# Sheet1.net
KiCad netlist of a schematic drawn in Altium Designer
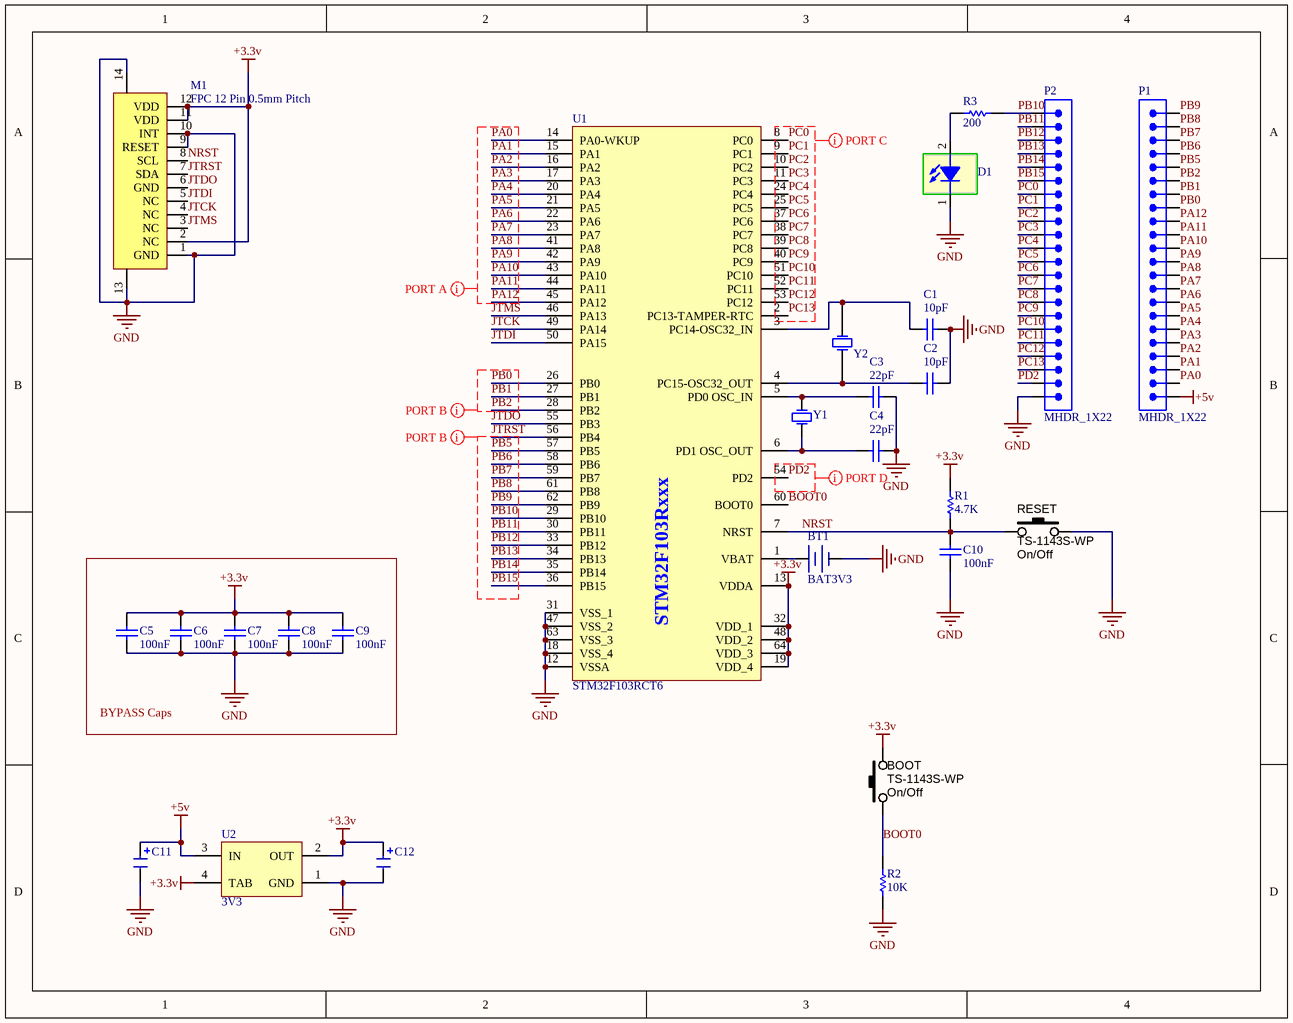
[diagram p0: Sheet1.SchDoc]

(export (version "E")
  (design (tool "Eeschema 10.0.6"))
  (components
    (comp (ref "BOOT")
      (value "TS-1143S-WP")
      (footprint "TS-1143S")
      (description "Switch SMD Tact 4.3mm Stem")
      (fields (field (name "FUNCTION") "On/Off"))
      (libsource (lib "Schematic") (part "SW_SMD_PB_4.3mm"))
    )
    (comp (ref "BT1")
      (value "BAT3V3")
      (footprint "Battery socket SMD")
      (description "Battry Backup")
      (fields (field (name "DESIGNER") "Abbas Basereh"))
      (libsource (lib "ALMA") (part "Battry Backup"))
    )
    (comp (ref "C1")
      (value "10pF")
      (footprint "0805 C")
      (description "CAP 0805")
      (fields (field (name "DESIGNER") "Abbas Basereh"))
      (libsource (lib "ALMA") (part "CAP SMD 0805"))
    )
    (comp (ref "C2")
      (value "10pF")
      (footprint "0805 C")
      (description "CAP 0805")
      (fields (field (name "DESIGNER") "Abbas Basereh"))
      (libsource (lib "ALMA") (part "CAP SMD 0805"))
    )
    (comp (ref "C3")
      (value "22pF")
      (footprint "0805 C")
      (description "CAP 0805")
      (fields (field (name "DESIGNER") "Abbas Basereh"))
      (libsource (lib "ALMA") (part "CAP SMD 0805"))
    )
    (comp (ref "C4")
      (value "22pF")
      (footprint "0805 C")
      (description "CAP 0805")
      (fields (field (name "DESIGNER") "Abbas Basereh"))
      (libsource (lib "ALMA") (part "CAP SMD 0805"))
    )
    (comp (ref "C5")
      (value "100nF")
      (footprint "0805 C")
      (description "CAP 0805")
      (fields (field (name "DESIGNER") "Abbas Basereh"))
      (libsource (lib "ALMA") (part "CAP SMD 0805"))
    )
    (comp (ref "C6")
      (value "100nF")
      (footprint "0805 C")
      (description "CAP 0805")
      (fields (field (name "DESIGNER") "Abbas Basereh"))
      (libsource (lib "ALMA") (part "CAP SMD 0805"))
    )
    (comp (ref "C7")
      (value "100nF")
      (footprint "0805 C")
      (description "CAP 0805")
      (fields (field (name "DESIGNER") "Abbas Basereh"))
      (libsource (lib "ALMA") (part "CAP SMD 0805"))
    )
    (comp (ref "C8")
      (value "100nF")
      (footprint "0805 C")
      (description "CAP 0805")
      (fields (field (name "DESIGNER") "Abbas Basereh"))
      (libsource (lib "ALMA") (part "CAP SMD 0805"))
    )
    (comp (ref "C9")
      (value "100nF")
      (footprint "0805 C")
      (description "CAP 0805")
      (fields (field (name "DESIGNER") "Abbas Basereh"))
      (libsource (lib "ALMA") (part "CAP SMD 0805"))
    )
    (comp (ref "C10")
      (value "100nF")
      (footprint "0805 C")
      (description "CAP 0805")
      (fields (field (name "DESIGNER") "Abbas Basereh"))
      (libsource (lib "ALMA") (part "CAP SMD 0805"))
    )
    (comp (ref "C11")
      (value "Tantalium Cap")
      (footprint "TANTAL-CAP-Size D")
      (libsource (lib "ALMA") (part "Capacitor Tantalium"))
    )
    (comp (ref "C12")
      (value "Tantalium Cap")
      (footprint "TANTAL-CAP-Size D")
      (libsource (lib "ALMA") (part "Capacitor Tantalium"))
    )
    (comp (ref "D1")
      (value "SMD 1206 LED")
      (footprint "LED 1206")
      (libsource (lib "Schematic") (part "LED SMD 1206"))
    )
    (comp (ref "M1")
      (value "FPC 12 Pin 0.5mm Pitch")
      (footprint "FPC 12 Pin 0.5mm Pitch")
      (libsource (lib "ZetaBoard_Lib") (part "FPC 12 Pin 0.5mm Pitch"))
    )
    (comp (ref "P1")
      (value "MHDR_1X22")
      (footprint "HDR1X22")
      (description "Male Header 1X22")
      (libsource (lib "Schematic") (part "MHDR_1X22"))
    )
    (comp (ref "P2")
      (value "MHDR_1X22")
      (footprint "HDR1X22")
      (description "Male Header 1X22")
      (libsource (lib "Schematic") (part "MHDR_1X22"))
    )
    (comp (ref "R1")
      (value "4.7K")
      (footprint "0805 R")
      (description "RES 0805")
      (fields (field (name "DESIGNER") "Abbas Basereh"))
      (libsource (lib "ALMA") (part "RES 0805 0.125W"))
    )
    (comp (ref "R2")
      (value "10K")
      (footprint "0805 R")
      (description "RES 0805")
      (fields (field (name "DESIGNER") "Abbas Basereh"))
      (libsource (lib "ALMA") (part "RES 0805 0.125W"))
    )
    (comp (ref "R3")
      (value "200")
      (footprint "0805 R")
      (description "RES 0805")
      (fields (field (name "DESIGNER") "Abbas Basereh"))
      (libsource (lib "ALMA") (part "RES 0805 0.125W"))
    )
    (comp (ref "RESET")
      (value "TS-1143S-WP")
      (footprint "TS-1143S")
      (description "Switch SMD Tact 4.3mm Stem")
      (fields (field (name "FUNCTION") "On/Off"))
      (libsource (lib "Schematic") (part "SW_SMD_PB_4.3mm"))
    )
    (comp (ref "U1")
      (value "STM32F103RCT6")
      (footprint "LQFP-64")
      (libsource (lib "ALMA") (part "STM32F103Rxxx"))
    )
    (comp (ref "U2")
      (value "3V3")
      (footprint "SOT223")
      (description "x.x Volt, 800mA Low-Dropout Linear Regulator, 4-pin SOT-223")
      (fields (field (name "DESIGNER") "Ali Hafizi"))
      (libsource (lib "Schematic") (part "AMS1117-x.x"))
    )
    (comp (ref "Y1")
      (value "16 MHz")
      (footprint "Xtal SMD")
      (description "XTAL Crystal")
      (fields (field (name "DESIGNER") "ABBAS BASEREH"))
      (libsource (lib "ALMA") (part "XTAL"))
    )
    (comp (ref "Y2")
      (value "11.0592 MHz")
      (footprint "Xtal 32.782khz")
      (description "XTAL Crystal")
      (fields (field (name "DESIGNER") "Eng. Saeid Jorablo") (field (name "PUBLISHER") "SJ Unlimited"))
      (libsource (lib "Schematic") (part "XTAL_Crystal"))
    )
  )
  (nets
    (net (code "1") (name "+3.3v") (class "Default")
      (node (ref "BOOT") (pin "2") (pintype "passive"))
      (node (ref "C12") (pin "1") (pintype "passive"))
      (node (ref "C5") (pin "1") (pinfunction "1_1") (pintype "passive"))
      (node (ref "C6") (pin "1") (pinfunction "1_1") (pintype "passive"))
      (node (ref "C7") (pin "1") (pinfunction "1_1") (pintype "passive"))
      (node (ref "C8") (pin "1") (pinfunction "1_1") (pintype "passive"))
      (node (ref "C9") (pin "1") (pinfunction "1_1") (pintype "passive"))
      (node (ref "M1") (pin "11") (pinfunction "VDD_11") (pintype "passive"))
      (node (ref "M1") (pin "12") (pinfunction "VDD_12") (pintype "passive"))
      (node (ref "M1") (pin "2") (pinfunction "NC_2") (pintype "passive"))
      (node (ref "R1") (pin "2") (pinfunction "2_2") (pintype "passive"))
      (node (ref "U1") (pin "13") (pinfunction "VDDA_13") (pintype "passive"))
      (node (ref "U1") (pin "19") (pinfunction "VDD_4_19") (pintype "passive"))
      (node (ref "U1") (pin "32") (pinfunction "VDD_1_32") (pintype "passive"))
      (node (ref "U1") (pin "48") (pinfunction "VDD_2_48") (pintype "passive"))
      (node (ref "U1") (pin "64") (pinfunction "VDD_3_64") (pintype "passive"))
      (node (ref "U2") (pin "2") (pinfunction "OUT_2") (pintype "power_in"))
      (node (ref "U2") (pin "4") (pinfunction "TAB_4") (pintype "power_in"))
    )
    (net (code "2") (name "+5v") (class "Default")
      (node (ref "C11") (pin "1") (pintype "passive"))
      (node (ref "P1") (pin "1") (pinfunction "1_1") (pintype "passive"))
      (node (ref "U2") (pin "3") (pinfunction "IN_3") (pintype "power_in"))
    )
    (net (code "3") (name "/BOOT0") (class "Default")
      (node (ref "BOOT") (pin "1") (pintype "passive"))
      (node (ref "R2") (pin "2") (pinfunction "2_2") (pintype "passive"))
      (node (ref "U1") (pin "60") (pinfunction "BOOT0_60") (pintype "passive"))
    )
    (net (code "4") (name "/JTCK") (class "Default")
      (node (ref "M1") (pin "4") (pinfunction "NC_4") (pintype "passive"))
      (node (ref "U1") (pin "49") (pinfunction "PA14_49") (pintype "passive"))
    )
    (net (code "5") (name "/JTDI") (class "Default")
      (node (ref "M1") (pin "5") (pinfunction "NC_5") (pintype "passive"))
      (node (ref "U1") (pin "50") (pinfunction "PA15_50") (pintype "passive"))
    )
    (net (code "6") (name "/JTDO") (class "Default")
      (node (ref "M1") (pin "6") (pinfunction "GND_6") (pintype "passive"))
      (node (ref "U1") (pin "55") (pinfunction "PB3_55") (pintype "passive"))
    )
    (net (code "7") (name "/JTMS") (class "Default")
      (node (ref "M1") (pin "3") (pinfunction "NC_3") (pintype "passive"))
      (node (ref "U1") (pin "46") (pinfunction "PA13_46") (pintype "passive"))
    )
    (net (code "8") (name "/JTRST") (class "Default")
      (node (ref "M1") (pin "7") (pinfunction "SDA_7") (pintype "passive"))
      (node (ref "U1") (pin "56") (pinfunction "PB4_56") (pintype "passive"))
    )
    (net (code "9") (name "/NRST") (class "Default")
      (node (ref "C10") (pin "1") (pinfunction "1_1") (pintype "passive"))
      (node (ref "M1") (pin "8") (pinfunction "SCL_8") (pintype "passive"))
      (node (ref "R1") (pin "1") (pinfunction "1_1") (pintype "passive"))
      (node (ref "RESET") (pin "1") (pintype "passive"))
      (node (ref "U1") (pin "7") (pinfunction "NRST_7") (pintype "passive"))
    )
    (net (code "10") (name "/PA0") (class "Default")
      (node (ref "P1") (pin "2") (pinfunction "2_2") (pintype "passive"))
      (node (ref "U1") (pin "14") (pinfunction "PA0-WKUP_14") (pintype "passive"))
    )
    (net (code "11") (name "/PA1") (class "Default")
      (node (ref "P1") (pin "3") (pinfunction "3_3") (pintype "passive"))
      (node (ref "U1") (pin "15") (pinfunction "PA1_15") (pintype "passive"))
    )
    (net (code "12") (name "/PA2") (class "Default")
      (node (ref "P1") (pin "4") (pinfunction "4_4") (pintype "passive"))
      (node (ref "U1") (pin "16") (pinfunction "PA2_16") (pintype "passive"))
    )
    (net (code "13") (name "/PA3") (class "Default")
      (node (ref "P1") (pin "5") (pinfunction "5_5") (pintype "passive"))
      (node (ref "U1") (pin "17") (pinfunction "PA3_17") (pintype "passive"))
    )
    (net (code "14") (name "/PA4") (class "Default")
      (node (ref "P1") (pin "6") (pinfunction "6_6") (pintype "passive"))
      (node (ref "U1") (pin "20") (pinfunction "PA4_20") (pintype "passive"))
    )
    (net (code "15") (name "/PA5") (class "Default")
      (node (ref "P1") (pin "7") (pinfunction "7_7") (pintype "passive"))
      (node (ref "U1") (pin "21") (pinfunction "PA5_21") (pintype "passive"))
    )
    (net (code "16") (name "/PA6") (class "Default")
      (node (ref "P1") (pin "8") (pinfunction "8_8") (pintype "passive"))
      (node (ref "U1") (pin "22") (pinfunction "PA6_22") (pintype "passive"))
    )
    (net (code "17") (name "/PA7") (class "Default")
      (node (ref "P1") (pin "9") (pinfunction "9_9") (pintype "passive"))
      (node (ref "U1") (pin "23") (pinfunction "PA7_23") (pintype "passive"))
    )
    (net (code "18") (name "/PA8") (class "Default")
      (node (ref "P1") (pin "10") (pinfunction "10_10") (pintype "passive"))
      (node (ref "U1") (pin "41") (pinfunction "PA8_41") (pintype "passive"))
    )
    (net (code "19") (name "/PA9") (class "Default")
      (node (ref "P1") (pin "11") (pinfunction "11_11") (pintype "passive"))
      (node (ref "U1") (pin "42") (pinfunction "PA9_42") (pintype "passive"))
    )
    (net (code "20") (name "/PA10") (class "Default")
      (node (ref "P1") (pin "12") (pinfunction "12_12") (pintype "passive"))
      (node (ref "U1") (pin "43") (pinfunction "PA10_43") (pintype "passive"))
    )
    (net (code "21") (name "/PA11") (class "Default")
      (node (ref "P1") (pin "13") (pinfunction "13_13") (pintype "passive"))
      (node (ref "U1") (pin "44") (pinfunction "PA11_44") (pintype "passive"))
    )
    (net (code "22") (name "/PA12") (class "Default")
      (node (ref "P1") (pin "14") (pinfunction "14_14") (pintype "passive"))
      (node (ref "U1") (pin "45") (pinfunction "PA12_45") (pintype "passive"))
    )
    (net (code "23") (name "/PB0") (class "Default")
      (node (ref "P1") (pin "15") (pinfunction "15_15") (pintype "passive"))
      (node (ref "U1") (pin "26") (pinfunction "PB0_26") (pintype "passive"))
    )
    (net (code "24") (name "/PB1") (class "Default")
      (node (ref "P1") (pin "16") (pinfunction "16_16") (pintype "passive"))
      (node (ref "U1") (pin "27") (pinfunction "PB1_27") (pintype "passive"))
    )
    (net (code "25") (name "/PB2") (class "Default")
      (node (ref "P1") (pin "17") (pinfunction "17_17") (pintype "passive"))
      (node (ref "U1") (pin "28") (pinfunction "PB2_28") (pintype "passive"))
    )
    (net (code "26") (name "/PB5") (class "Default")
      (node (ref "P1") (pin "18") (pinfunction "18_18") (pintype "passive"))
      (node (ref "U1") (pin "57") (pinfunction "PB5_57") (pintype "passive"))
    )
    (net (code "27") (name "/PB6") (class "Default")
      (node (ref "P1") (pin "19") (pinfunction "19_19") (pintype "passive"))
      (node (ref "U1") (pin "58") (pinfunction "PB6_58") (pintype "passive"))
    )
    (net (code "28") (name "/PB7") (class "Default")
      (node (ref "P1") (pin "20") (pinfunction "20_20") (pintype "passive"))
      (node (ref "U1") (pin "59") (pinfunction "PB7_59") (pintype "passive"))
    )
    (net (code "29") (name "/PB8") (class "Default")
      (node (ref "P1") (pin "21") (pinfunction "21_21") (pintype "passive"))
      (node (ref "U1") (pin "61") (pinfunction "PB8_61") (pintype "passive"))
    )
    (net (code "30") (name "/PB9") (class "Default")
      (node (ref "P1") (pin "22") (pinfunction "22_22") (pintype "passive"))
      (node (ref "U1") (pin "62") (pinfunction "PB9_62") (pintype "passive"))
    )
    (net (code "31") (name "/PB10") (class "Default")
      (node (ref "P2") (pin "1") (pinfunction "1_1") (pintype "passive"))
      (node (ref "R3") (pin "1") (pinfunction "1_1") (pintype "passive"))
      (node (ref "U1") (pin "29") (pinfunction "PB10_29") (pintype "passive"))
    )
    (net (code "32") (name "/PB11") (class "Default")
      (node (ref "P2") (pin "2") (pinfunction "2_2") (pintype "passive"))
      (node (ref "U1") (pin "30") (pinfunction "PB11_30") (pintype "passive"))
    )
    (net (code "33") (name "/PB12") (class "Default")
      (node (ref "P2") (pin "3") (pinfunction "3_3") (pintype "passive"))
      (node (ref "U1") (pin "33") (pinfunction "PB12_33") (pintype "passive"))
    )
    (net (code "34") (name "/PB13") (class "Default")
      (node (ref "P2") (pin "4") (pinfunction "4_4") (pintype "passive"))
      (node (ref "U1") (pin "34") (pinfunction "PB13_34") (pintype "passive"))
    )
    (net (code "35") (name "/PB14") (class "Default")
      (node (ref "P2") (pin "5") (pinfunction "5_5") (pintype "passive"))
      (node (ref "U1") (pin "35") (pinfunction "PB14_35") (pintype "passive"))
    )
    (net (code "36") (name "/PB15") (class "Default")
      (node (ref "P2") (pin "6") (pinfunction "6_6") (pintype "passive"))
      (node (ref "U1") (pin "36") (pinfunction "PB15_36") (pintype "passive"))
    )
    (net (code "37") (name "/PC0") (class "Default")
      (node (ref "P2") (pin "7") (pinfunction "7_7") (pintype "passive"))
      (node (ref "U1") (pin "8") (pinfunction "PC0_8") (pintype "passive"))
    )
    (net (code "38") (name "/PC1") (class "Default")
      (node (ref "P2") (pin "8") (pinfunction "8_8") (pintype "passive"))
      (node (ref "U1") (pin "9") (pinfunction "PC1_9") (pintype "passive"))
    )
    (net (code "39") (name "/PC2") (class "Default")
      (node (ref "P2") (pin "9") (pinfunction "9_9") (pintype "passive"))
      (node (ref "U1") (pin "10") (pinfunction "PC2_10") (pintype "passive"))
    )
    (net (code "40") (name "/PC3") (class "Default")
      (node (ref "P2") (pin "10") (pinfunction "10_10") (pintype "passive"))
      (node (ref "U1") (pin "11") (pinfunction "PC3_11") (pintype "passive"))
    )
    (net (code "41") (name "/PC4") (class "Default")
      (node (ref "P2") (pin "11") (pinfunction "11_11") (pintype "passive"))
      (node (ref "U1") (pin "24") (pinfunction "PC4_24") (pintype "passive"))
    )
    (net (code "42") (name "/PC5") (class "Default")
      (node (ref "P2") (pin "12") (pinfunction "12_12") (pintype "passive"))
      (node (ref "U1") (pin "25") (pinfunction "PC5_25") (pintype "passive"))
    )
    (net (code "43") (name "/PC6") (class "Default")
      (node (ref "P2") (pin "13") (pinfunction "13_13") (pintype "passive"))
      (node (ref "U1") (pin "37") (pinfunction "PC6_37") (pintype "passive"))
    )
    (net (code "44") (name "/PC7") (class "Default")
      (node (ref "P2") (pin "14") (pinfunction "14_14") (pintype "passive"))
      (node (ref "U1") (pin "38") (pinfunction "PC7_38") (pintype "passive"))
    )
    (net (code "45") (name "/PC8") (class "Default")
      (node (ref "P2") (pin "15") (pinfunction "15_15") (pintype "passive"))
      (node (ref "U1") (pin "39") (pinfunction "PC8_39") (pintype "passive"))
    )
    (net (code "46") (name "/PC9") (class "Default")
      (node (ref "P2") (pin "16") (pinfunction "16_16") (pintype "passive"))
      (node (ref "U1") (pin "40") (pinfunction "PC9_40") (pintype "passive"))
    )
    (net (code "47") (name "/PC10") (class "Default")
      (node (ref "P2") (pin "17") (pinfunction "17_17") (pintype "passive"))
      (node (ref "U1") (pin "51") (pinfunction "PC10_51") (pintype "passive"))
    )
    (net (code "48") (name "/PC11") (class "Default")
      (node (ref "P2") (pin "18") (pinfunction "18_18") (pintype "passive"))
      (node (ref "U1") (pin "52") (pinfunction "PC11_52") (pintype "passive"))
    )
    (net (code "49") (name "/PC12") (class "Default")
      (node (ref "P2") (pin "19") (pinfunction "19_19") (pintype "passive"))
      (node (ref "U1") (pin "53") (pinfunction "PC12_53") (pintype "passive"))
    )
    (net (code "50") (name "/PC13") (class "Default")
      (node (ref "P2") (pin "20") (pinfunction "20_20") (pintype "passive"))
      (node (ref "U1") (pin "2") (pinfunction "PC13-TAMPER-RTC_2") (pintype "passive"))
    )
    (net (code "51") (name "/PD2") (class "Default")
      (node (ref "P2") (pin "21") (pinfunction "21_21") (pintype "passive"))
      (node (ref "U1") (pin "54") (pinfunction "PD2_54") (pintype "passive"))
    )
    (net (code "52") (name "GND") (class "Default")
      (node (ref "BT1") (pin "2") (pinfunction "-_2") (pintype "passive"))
      (node (ref "C1") (pin "1") (pinfunction "1_1") (pintype "passive"))
      (node (ref "C10") (pin "2") (pinfunction "2_2") (pintype "passive"))
      (node (ref "C11") (pin "2") (pintype "passive"))
      (node (ref "C12") (pin "2") (pintype "passive"))
      (node (ref "C2") (pin "1") (pinfunction "1_1") (pintype "passive"))
      (node (ref "C3") (pin "1") (pinfunction "1_1") (pintype "passive"))
      (node (ref "C4") (pin "1") (pinfunction "1_1") (pintype "passive"))
      (node (ref "C5") (pin "2") (pinfunction "2_2") (pintype "passive"))
      (node (ref "C6") (pin "2") (pinfunction "2_2") (pintype "passive"))
      (node (ref "C7") (pin "2") (pinfunction "2_2") (pintype "passive"))
      (node (ref "C8") (pin "2") (pinfunction "2_2") (pintype "passive"))
      (node (ref "C9") (pin "2") (pinfunction "2_2") (pintype "passive"))
      (node (ref "D1") (pin "1") (pinfunction "1_1") (pintype "passive"))
      (node (ref "M1") (pin "1") (pinfunction "GND_1") (pintype "passive"))
      (node (ref "M1") (pin "10") (pinfunction "INT_10") (pintype "passive"))
      (node (ref "M1") (pin "13") (pinfunction "NC_13") (pintype "passive"))
      (node (ref "M1") (pin "14") (pinfunction "NC_14") (pintype "passive"))
      (node (ref "M1") (pin "9") (pinfunction "RESET_9") (pintype "passive"))
      (node (ref "P2") (pin "22") (pinfunction "22_22") (pintype "passive"))
      (node (ref "R2") (pin "1") (pinfunction "1_1") (pintype "passive"))
      (node (ref "RESET") (pin "2") (pintype "passive"))
      (node (ref "U1") (pin "12") (pinfunction "VSSA_12") (pintype "passive"))
      (node (ref "U1") (pin "18") (pinfunction "VSS_4_18") (pintype "passive"))
      (node (ref "U1") (pin "31") (pinfunction "VSS_1_31") (pintype "passive"))
      (node (ref "U1") (pin "47") (pinfunction "VSS_2_47") (pintype "passive"))
      (node (ref "U1") (pin "63") (pinfunction "VSS_3_63") (pintype "passive"))
      (node (ref "U2") (pin "1") (pinfunction "GND_1") (pintype "power_in"))
    )
    (net (code "53") (name "Net-(BT1-+)") (class "Default")
      (node (ref "BT1") (pin "1") (pinfunction "+_1") (pintype "passive"))
      (node (ref "U1") (pin "1") (pinfunction "VBAT_1") (pintype "passive"))
    )
    (net (code "54") (name "Net-(D1-Pad2)") (class "Default")
      (node (ref "D1") (pin "2") (pinfunction "2_2") (pintype "passive"))
      (node (ref "R3") (pin "2") (pinfunction "2_2") (pintype "passive"))
    )
    (net (code "55") (name "Net-(U1-PC14-OSC32_IN)") (class "Default")
      (node (ref "C1") (pin "2") (pinfunction "2_2") (pintype "passive"))
      (node (ref "U1") (pin "3") (pinfunction "PC14-OSC32_IN_3") (pintype "passive"))
      (node (ref "Y2") (pin "2") (pinfunction "OSC2_2") (pintype "passive"))
    )
    (net (code "56") (name "Net-(U1-PC15-OSC32_OUT)") (class "Default")
      (node (ref "C2") (pin "2") (pinfunction "2_2") (pintype "passive"))
      (node (ref "U1") (pin "4") (pinfunction "PC15-OSC32_OUT_4") (pintype "passive"))
      (node (ref "Y2") (pin "1") (pinfunction "OSC1_1") (pintype "passive"))
    )
    (net (code "57") (name "Net-(U1-PD0_OSC_IN)") (class "Default")
      (node (ref "C3") (pin "2") (pinfunction "2_2") (pintype "passive"))
      (node (ref "U1") (pin "5") (pinfunction "PD0_OSC_IN_5") (pintype "passive"))
      (node (ref "Y1") (pin "2") (pinfunction "OSC2_2") (pintype "passive"))
    )
    (net (code "58") (name "Net-(U1-PD1_OSC_OUT)") (class "Default")
      (node (ref "C4") (pin "2") (pinfunction "2_2") (pintype "passive"))
      (node (ref "U1") (pin "6") (pinfunction "PD1_OSC_OUT_6") (pintype "passive"))
      (node (ref "Y1") (pin "1") (pinfunction "OSC1_1") (pintype "passive"))
    )
  )
)
